# serial.net
KiCad netlist of a schematic drawn in Altium Designer
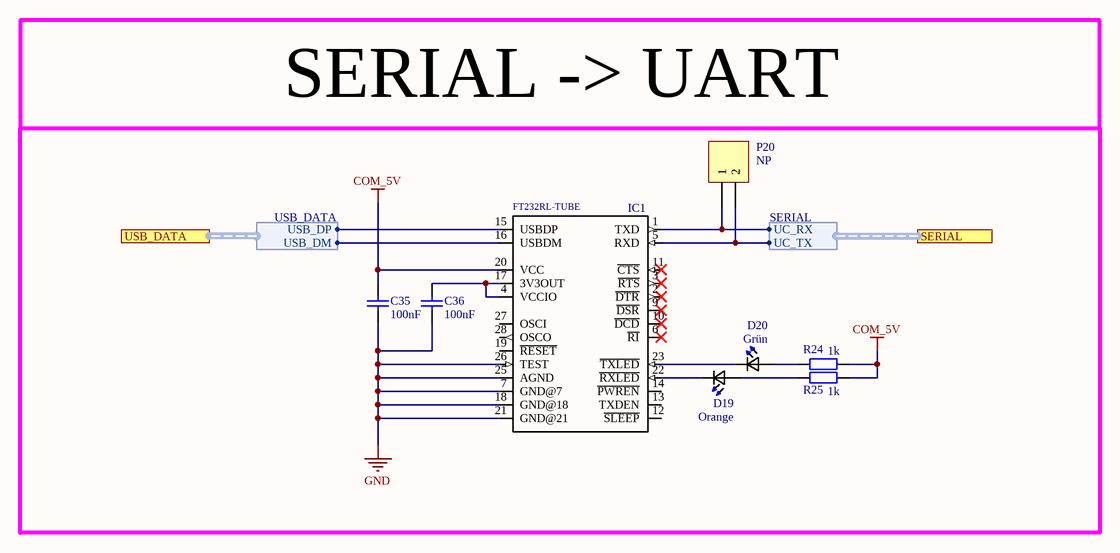
[diagram p0: serial.SchDoc]

(export (version "E")
  (design (tool "Eeschema 10.0.6"))
  (components
    (comp (ref "C35")
      (value "100nF")
      (footprint "CAP_0402i_1005m -N")
      (description "capacitor")
      (libsource (lib "IDSC std generic parts") (part "Cap"))
    )
    (comp (ref "C36")
      (value "100nF")
      (footprint "CAP_0402i_1005m -N")
      (description "capacitor")
      (libsource (lib "IDSC std generic parts") (part "Cap"))
    )
    (comp (ref "D19")
      (value "Orange")
      (footprint "*0603")
      (description "LED; SMD; 0603; orange; 45-90mcd; 1.6x0.8x0.55mm; 130Â°; 2Ã·2.4V; 20mA")
      (fields (field (name "MP") "LTST-C191KFKT") (field (name "DIGI-KEY_PART_NUMBER") "160-1445-1-ND"))
      (libsource (lib "Funk") (part "LTST-C191KFKT"))
    )
    (comp (ref "D20")
      (value "Grün")
      (footprint "*0603")
      (description "LED; SMD; 0603; gr黱; 35mcd; 1.6x0.8x0.55mm; 130掳; 2梅2.V; 20mA")
      (fields (field (name "MP") "LTST-C191KGKT") (field (name "DIGI-KEY_PART_NUMBER") "160-1446-1-ND"))
      (libsource (lib "Funk") (part "LTST-C191KGKT"))
    )
    (comp (ref "IC1")
      (value "FT232RL-TUBE")
      (footprint "*SSOP28-LD")
      (description "USB-to-UART 1-CH 256byte FIFO 5V 28-Pin SSOP Tube")
      (fields (field (name "DIGI-KEY_PART_NUMBER") "768-1306-ND") (field (name "MF") "FTDI,"))
      (libsource (lib "Funk") (part "FT232RL-TUBE"))
    )
    (comp (ref "P20")
      (value "NP")
      (footprint "HDR1X2")
      (description "Header, 2-Pin")
      (libsource (lib "IDSC std connectors") (part "Header 2"))
    )
    (comp (ref "R24")
      (value "1k")
      (footprint "RES_0603i_1608m -N")
      (description "Resistor")
      (libsource (lib "IDSC std generic parts") (part "Res"))
    )
    (comp (ref "R25")
      (value "1k")
      (footprint "RES_0603i_1608m -N")
      (description "Resistor")
      (libsource (lib "IDSC std generic parts") (part "Res"))
    )
  )
  (nets
    (net (code "3") (name "/UC_RX") (class "Default")
      (node (ref "IC1") (pin "1") (pinfunction "TXD_1") (pintype "output"))
      (node (ref "P20") (pin "1") (pinfunction "1_1") (pintype "passive"))
    )
    (net (code "4") (name "/UC_TX") (class "Default")
      (node (ref "IC1") (pin "5") (pinfunction "RXD_5") (pintype "input"))
      (node (ref "P20") (pin "2") (pinfunction "2_2") (pintype "passive"))
    )
    (net (code "5") (name "/USB_DM") (class "Default")
      (node (ref "IC1") (pin "16") (pinfunction "USBDM_16") (pintype "bidirectional"))
    )
    (net (code "6") (name "/USB_DP") (class "Default")
      (node (ref "IC1") (pin "15") (pinfunction "USBDP_15") (pintype "bidirectional"))
    )
    (net (code "9") (name "COM_5V") (class "Default")
      (node (ref "C35") (pin "2") (pinfunction "2_2") (pintype "passive"))
      (node (ref "IC1") (pin "20") (pinfunction "VCC_20") (pintype "power_in"))
      (node (ref "R24") (pin "2") (pinfunction "2_2") (pintype "passive"))
      (node (ref "R25") (pin "2") (pinfunction "2_2") (pintype "passive"))
    )
    (net (code "10") (name "GND") (class "Default")
      (node (ref "C35") (pin "1") (pinfunction "1_1") (pintype "passive"))
      (node (ref "C36") (pin "1") (pinfunction "1_1") (pintype "passive"))
      (node (ref "IC1") (pin "18") (pinfunction "GND@18_18") (pintype "power_in"))
      (node (ref "IC1") (pin "21") (pinfunction "GND@21_21") (pintype "power_in"))
      (node (ref "IC1") (pin "25") (pinfunction "AGND_25") (pintype "power_in"))
      (node (ref "IC1") (pin "26") (pinfunction "TEST_26") (pintype "input"))
      (node (ref "IC1") (pin "7") (pinfunction "GND@7_7") (pintype "power_in"))
    )
    (net (code "11") (name "Net-(D19-A2)") (class "Default")
      (node (ref "D19") (pin "2") (pinfunction "A2_2") (pintype "passive"))
      (node (ref "R25") (pin "1") (pinfunction "1_1") (pintype "passive"))
    )
    (net (code "12") (name "Net-(D19-K2)") (class "Default")
      (node (ref "D19") (pin "1") (pinfunction "K2_1") (pintype "passive"))
      (node (ref "IC1") (pin "22") (pinfunction "~{RXLED}_22") (pintype "input"))
    )
    (net (code "13") (name "Net-(D20-A2)") (class "Default")
      (node (ref "D20") (pin "2") (pinfunction "A2_2") (pintype "passive"))
      (node (ref "R24") (pin "1") (pinfunction "1_1") (pintype "passive"))
    )
    (net (code "14") (name "Net-(D20-K2)") (class "Default")
      (node (ref "D20") (pin "1") (pinfunction "K2_1") (pintype "passive"))
      (node (ref "IC1") (pin "23") (pinfunction "~{TXLED}_23") (pintype "input"))
    )
    (net (code "15") (name "Net-(IC1-3V3OUT)") (class "Default")
      (node (ref "C36") (pin "2") (pinfunction "2_2") (pintype "passive"))
      (node (ref "IC1") (pin "17") (pinfunction "3V3OUT_17") (pintype "power_in"))
      (node (ref "IC1") (pin "4") (pinfunction "VCCIO_4") (pintype "power_in"))
    )
    (net (code "16") (name "unconnected-(IC1-OSCI-Pad27)") (class "Default")
      (node (ref "IC1") (pin "27") (pinfunction "OSCI_27") (pintype "passive"))
    )
    (net (code "17") (name "unconnected-(IC1-OSCO-Pad28)") (class "Default")
      (node (ref "IC1") (pin "28") (pinfunction "OSCO_28") (pintype "output"))
    )
    (net (code "18") (name "unconnected-(IC1-TXDEN-Pad13)") (class "Default")
      (node (ref "IC1") (pin "13") (pinfunction "TXDEN_13") (pintype "passive"))
    )
    (net (code "19") (name "unconnected-(IC1-~{CTS}-Pad11)") (class "Default")
      (node (ref "IC1") (pin "11") (pinfunction "~{CTS}_11") (pintype "input+no_connect"))
    )
    (net (code "20") (name "unconnected-(IC1-~{DCD}-Pad10)") (class "Default")
      (node (ref "IC1") (pin "10") (pinfunction "~{DCD}_10") (pintype "passive+no_connect"))
    )
    (net (code "21") (name "unconnected-(IC1-~{DSR}-Pad9)") (class "Default")
      (node (ref "IC1") (pin "9") (pinfunction "~{DSR}_9") (pintype "passive+no_connect"))
    )
    (net (code "22") (name "unconnected-(IC1-~{DTR}-Pad2)") (class "Default")
      (node (ref "IC1") (pin "2") (pinfunction "~{DTR}_2") (pintype "output+no_connect"))
    )
    (net (code "23") (name "unconnected-(IC1-~{PWREN}-Pad14)") (class "Default")
      (node (ref "IC1") (pin "14") (pinfunction "~{PWREN}_14") (pintype "passive"))
    )
    (net (code "24") (name "unconnected-(IC1-~{RESET}-Pad19)") (class "Default")
      (node (ref "IC1") (pin "19") (pinfunction "~{RESET}_19") (pintype "passive"))
    )
    (net (code "25") (name "unconnected-(IC1-~{RI}-Pad6)") (class "Default")
      (node (ref "IC1") (pin "6") (pinfunction "~{RI}_6") (pintype "passive+no_connect"))
    )
    (net (code "26") (name "unconnected-(IC1-~{RTS}-Pad3)") (class "Default")
      (node (ref "IC1") (pin "3") (pinfunction "~{RTS}_3") (pintype "output+no_connect"))
    )
    (net (code "27") (name "unconnected-(IC1-~{SLEEP}-Pad12)") (class "Default")
      (node (ref "IC1") (pin "12") (pinfunction "~{SLEEP}_12") (pintype "passive"))
    )
  )
)
